# ts-7553-v2-xbee-door-alarm-simple.net
KiCad netlist of a schematic drawn in EAGLE
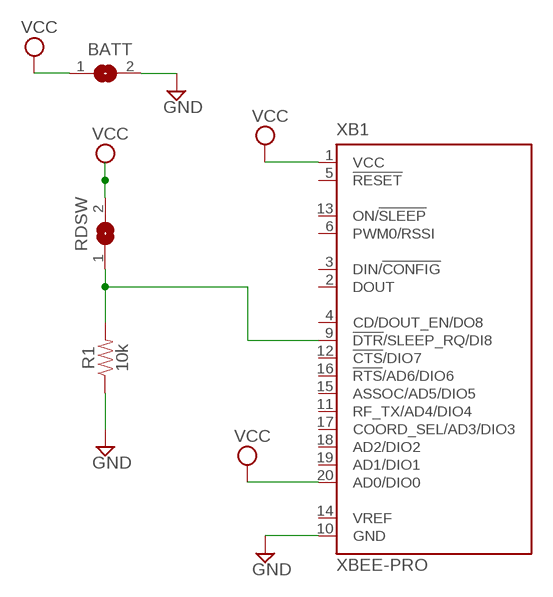
[diagram p0: schematic, sheet 1]

(export (version "E")
  (design (tool "Eeschema 10.0.6"))
  (components
    (comp (ref "BATT")
      (value "SJW")
      (footprint "eagle-import:SJW")
      (libsource (lib "eagle-import") (part "SJW"))
    )
    (comp (ref "R1")
      (value "10k")
      (footprint "eagle-import:AXIAL-0.3")
      (libsource (lib "eagle-import") (part "10KOHM-HORIZ-1/4W-5%"))
    )
    (comp (ref "RDSW")
      (value "SJW")
      (footprint "eagle-import:SJW")
      (libsource (lib "eagle-import") (part "SJW"))
    )
    (comp (ref "XB1")
      (value "XBEE-PRO")
      (footprint "eagle-import:XBEE-PRO")
      (fields (field (name "MPN") "XBP24-AWI-001"))
      (libsource (lib "eagle-import") (part "XBEE-PRO"))
    )
  )
  (nets
    (net (code "1") (name "GND") (class "Default")
      (node (ref "BATT") (pin "2") (pinfunction "2_2") (pintype "passive"))
      (node (ref "R1") (pin "P$1") (pinfunction "1_P$1") (pintype "passive"))
      (node (ref "XB1") (pin "10") (pinfunction "GND_10") (pintype "power_in"))
    )
    (net (code "2") (name "Net-(R1-2)") (class "Default")
      (node (ref "R1") (pin "P$2") (pinfunction "2_P$2") (pintype "passive"))
      (node (ref "RDSW") (pin "1") (pinfunction "1_1") (pintype "passive"))
      (node (ref "XB1") (pin "9") (pinfunction "~{DTR}/SLEEP_RQ/DI8_9") (pintype "bidirectional"))
    )
    (net (code "3") (name "VCC") (class "Default")
      (node (ref "BATT") (pin "1") (pinfunction "1_1") (pintype "passive"))
      (node (ref "RDSW") (pin "2") (pinfunction "2_2") (pintype "passive"))
      (node (ref "XB1") (pin "1") (pinfunction "VCC_1") (pintype "power_in"))
      (node (ref "XB1") (pin "20") (pinfunction "AD0/DIO0_20") (pintype "bidirectional"))
    )
    (net (code "4") (name "unconnected-(XB1-AD1{slash}DIO1-Pad19)") (class "Default")
      (node (ref "XB1") (pin "19") (pinfunction "AD1/DIO1_19") (pintype "bidirectional"))
    )
    (net (code "5") (name "unconnected-(XB1-AD2{slash}DIO2-Pad18)") (class "Default")
      (node (ref "XB1") (pin "18") (pinfunction "AD2/DIO2_18") (pintype "bidirectional"))
    )
    (net (code "6") (name "unconnected-(XB1-ASSOC{slash}AD5{slash}DIO5-Pad15)") (class "Default")
      (node (ref "XB1") (pin "15") (pinfunction "ASSOC/AD5/DIO5_15") (pintype "bidirectional"))
    )
    (net (code "7") (name "unconnected-(XB1-CD{slash}DOUT_EN{slash}DO8-Pad4)") (class "Default")
      (node (ref "XB1") (pin "4") (pinfunction "CD/DOUT_EN/DO8_4") (pintype "output"))
    )
    (net (code "8") (name "unconnected-(XB1-COORD_SEL{slash}AD3{slash}DIO3-Pad17)") (class "Default")
      (node (ref "XB1") (pin "17") (pinfunction "COORD_SEL/AD3/DIO3_17") (pintype "bidirectional"))
    )
    (net (code "9") (name "unconnected-(XB1-DIN{slash}~{CONFIG}-Pad3)") (class "Default")
      (node (ref "XB1") (pin "3") (pinfunction "DIN/~{CONFIG}_3") (pintype "input"))
    )
    (net (code "10") (name "unconnected-(XB1-DOUT-Pad2)") (class "Default")
      (node (ref "XB1") (pin "2") (pinfunction "DOUT_2") (pintype "output"))
    )
    (net (code "11") (name "unconnected-(XB1-ON{slash}~{SLEEP}-Pad13)") (class "Default")
      (node (ref "XB1") (pin "13") (pinfunction "ON/~{SLEEP}_13") (pintype "output"))
    )
    (net (code "12") (name "unconnected-(XB1-PWM0{slash}RSSI-Pad6)") (class "Default")
      (node (ref "XB1") (pin "6") (pinfunction "PWM0/RSSI_6") (pintype "output"))
    )
    (net (code "13") (name "unconnected-(XB1-RF_TX{slash}AD4{slash}DIO4-Pad11)") (class "Default")
      (node (ref "XB1") (pin "11") (pinfunction "RF_TX/AD4/DIO4_11") (pintype "bidirectional"))
    )
    (net (code "14") (name "unconnected-(XB1-VREF-Pad14)") (class "Default")
      (node (ref "XB1") (pin "14") (pinfunction "VREF_14") (pintype "input"))
    )
    (net (code "15") (name "unconnected-(XB1-~{CTS}{slash}DIO7-Pad12)") (class "Default")
      (node (ref "XB1") (pin "12") (pinfunction "~{CTS}/DIO7_12") (pintype "bidirectional"))
    )
    (net (code "16") (name "unconnected-(XB1-~{RESET}-Pad5)") (class "Default")
      (node (ref "XB1") (pin "5") (pinfunction "~{RESET}_5") (pintype "input"))
    )
    (net (code "17") (name "unconnected-(XB1-~{RTS}{slash}AD6{slash}DIO6-Pad16)") (class "Default")
      (node (ref "XB1") (pin "16") (pinfunction "~{RTS}/AD6/DIO6_16") (pintype "bidirectional"))
    )
  )
)
